# OUTPUT.net
KiCad netlist of a schematic drawn in Altium Designer
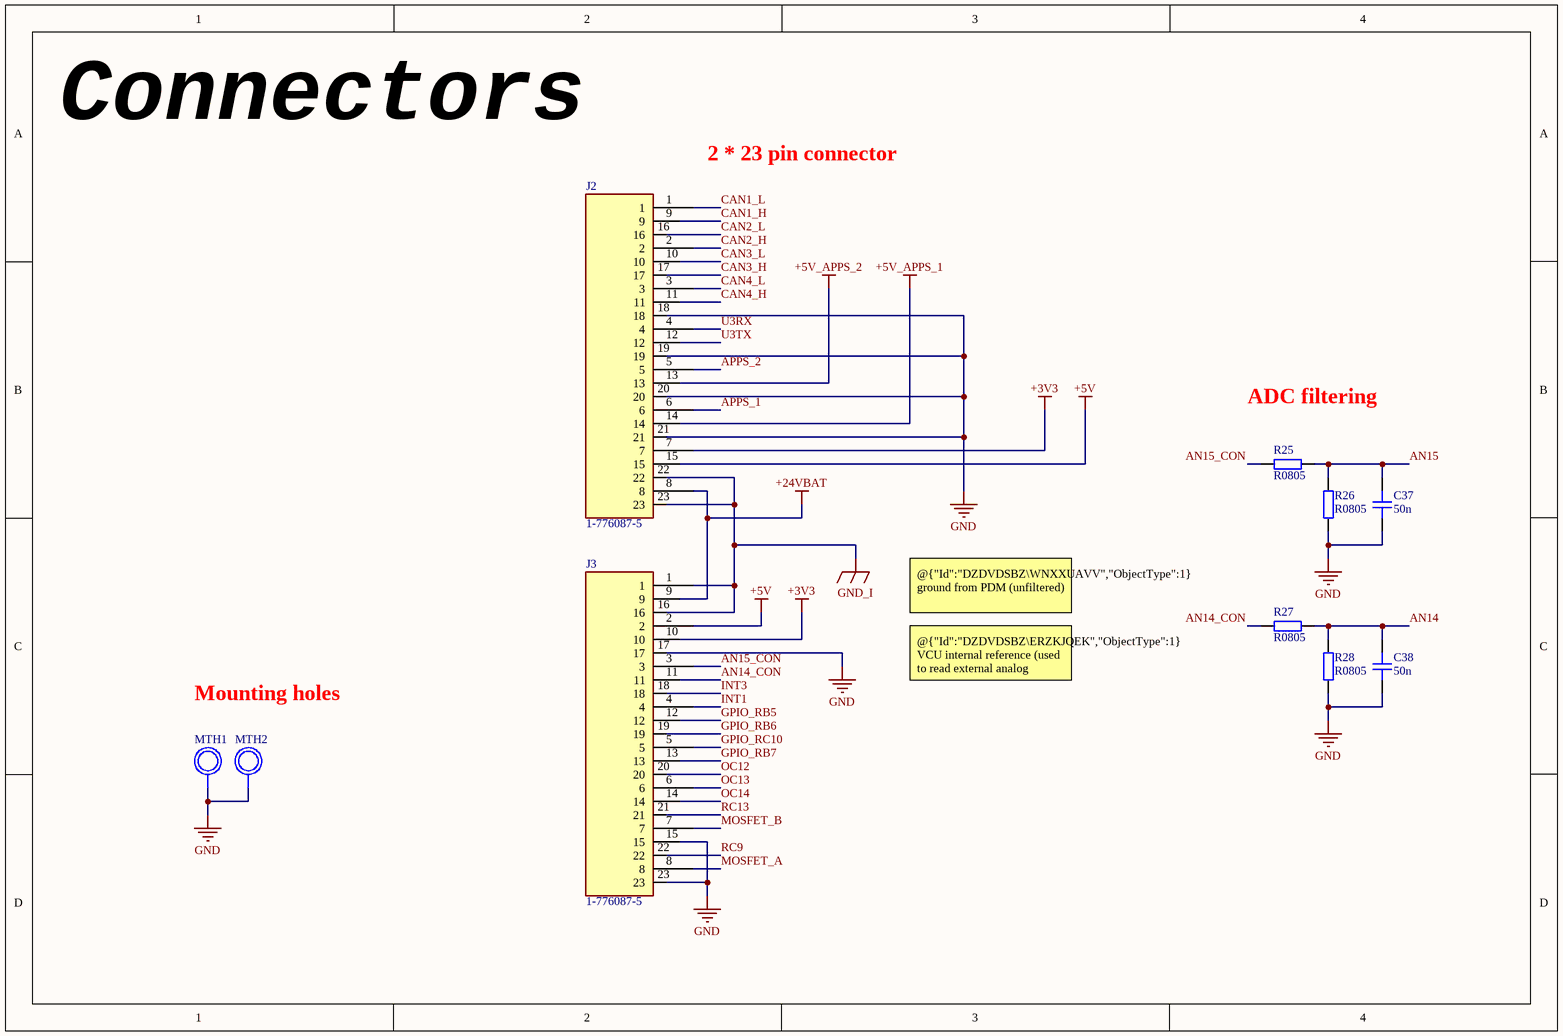
[diagram p0: OUTPUT.SchDoc]

(export (version "E")
  (design (tool "Eeschema 10.0.6"))
  (components
    (comp (ref "C37")
      (value "50n")
      (footprint "CAP_0805")
      (description "Capacitor SMD 0805 10V")
      (libsource (lib "Schematic-Lib-PhilsLab") (part "CAP_0805_10V"))
    )
    (comp (ref "C38")
      (value "50n")
      (footprint "CAP_0805")
      (description "Capacitor SMD 0805 10V")
      (libsource (lib "Schematic-Lib-PhilsLab") (part "CAP_0805_10V"))
    )
    (comp (ref "J2")
      (value "1-776087-5")
      (footprint "1-776087-5")
      (description "CONN HDR 23POS R/A W/GASKET AU")
      (libsource (lib "Pedro_Integrated_Library") (part "1-776087-5"))
    )
    (comp (ref "J3")
      (value "1-776087-5")
      (footprint "1-776087-5")
      (description "CONN HDR 23POS R/A W/GASKET AU")
      (libsource (lib "Pedro_Integrated_Library") (part "1-776087-5"))
    )
    (comp (ref "MTH1")
      (value "Mounting_Hole_3.5mm")
      (footprint "Mounting_Hole_3.5mm")
      (libsource (lib "Pedro_Integrated_Library") (part "Mounting_Hole_3.5mm"))
    )
    (comp (ref "MTH2")
      (value "Mounting_Hole_3.5mm")
      (footprint "Mounting_Hole_3.5mm")
      (libsource (lib "Pedro_Integrated_Library") (part "Mounting_Hole_3.5mm"))
    )
    (comp (ref "R25")
      (value "R0805")
      (footprint "RES_0805")
      (description "Resistor SMD 0805")
      (libsource (lib "Schematic-Lib-PhilsLab") (part "RES_0805"))
    )
    (comp (ref "R26")
      (value "R0805")
      (footprint "RES_0805")
      (description "Resistor SMD 0805")
      (libsource (lib "Schematic-Lib-PhilsLab") (part "RES_0805"))
    )
    (comp (ref "R27")
      (value "R0805")
      (footprint "RES_0805")
      (description "Resistor SMD 0805")
      (libsource (lib "Schematic-Lib-PhilsLab") (part "RES_0805"))
    )
    (comp (ref "R28")
      (value "R0805")
      (footprint "RES_0805")
      (description "Resistor SMD 0805")
      (libsource (lib "Schematic-Lib-PhilsLab") (part "RES_0805"))
    )
  )
  (nets
    (net (code "1") (name "+3V3") (class "Default")
      (node (ref "J2") (pin "7") (pinfunction "7_7") (pintype "passive"))
      (node (ref "J3") (pin "10") (pinfunction "10_10") (pintype "passive"))
    )
    (net (code "2") (name "+5V") (class "Default")
      (node (ref "J2") (pin "15") (pinfunction "15_15") (pintype "passive"))
      (node (ref "J3") (pin "2") (pinfunction "2_2") (pintype "passive"))
    )
    (net (code "3") (name "+5V_APPS_1") (class "Default")
      (node (ref "J2") (pin "14") (pinfunction "14_14") (pintype "passive"))
    )
    (net (code "4") (name "+5V_APPS_2") (class "Default")
      (node (ref "J2") (pin "13") (pinfunction "13_13") (pintype "passive"))
    )
    (net (code "5") (name "+24VBAT") (class "Default")
      (node (ref "J2") (pin "8") (pinfunction "8_8") (pintype "passive"))
      (node (ref "J3") (pin "9") (pinfunction "9_9") (pintype "passive"))
    )
    (net (code "6") (name "/AN14") (class "Default")
      (node (ref "C38") (pin "1") (pinfunction "1_1") (pintype "passive"))
      (node (ref "R27") (pin "1") (pinfunction "1_1") (pintype "passive"))
      (node (ref "R28") (pin "1") (pinfunction "1_1") (pintype "passive"))
    )
    (net (code "7") (name "/AN14_CON") (class "Default")
      (node (ref "J3") (pin "11") (pinfunction "11_11") (pintype "passive"))
      (node (ref "R27") (pin "2") (pinfunction "2_2") (pintype "passive"))
    )
    (net (code "8") (name "/AN15") (class "Default")
      (node (ref "C37") (pin "1") (pinfunction "1_1") (pintype "passive"))
      (node (ref "R25") (pin "1") (pinfunction "1_1") (pintype "passive"))
      (node (ref "R26") (pin "1") (pinfunction "1_1") (pintype "passive"))
    )
    (net (code "9") (name "/AN15_CON") (class "Default")
      (node (ref "J3") (pin "3") (pinfunction "3_3") (pintype "passive"))
      (node (ref "R25") (pin "2") (pinfunction "2_2") (pintype "passive"))
    )
    (net (code "10") (name "/APPS_1") (class "Default")
      (node (ref "J2") (pin "6") (pinfunction "6_6") (pintype "passive"))
    )
    (net (code "11") (name "/APPS_2") (class "Default")
      (node (ref "J2") (pin "5") (pinfunction "5_5") (pintype "passive"))
    )
    (net (code "12") (name "/CAN1_H") (class "Default")
      (node (ref "J2") (pin "9") (pinfunction "9_9") (pintype "passive"))
    )
    (net (code "13") (name "/CAN1_L") (class "Default")
      (node (ref "J2") (pin "1") (pinfunction "1_1") (pintype "passive"))
    )
    (net (code "14") (name "/CAN2_H") (class "Default")
      (node (ref "J2") (pin "2") (pinfunction "2_2") (pintype "passive"))
    )
    (net (code "15") (name "/CAN2_L") (class "Default")
      (node (ref "J2") (pin "16") (pinfunction "16_16") (pintype "passive"))
    )
    (net (code "16") (name "/CAN3_H") (class "Default")
      (node (ref "J2") (pin "17") (pinfunction "17_17") (pintype "passive"))
    )
    (net (code "17") (name "/CAN3_L") (class "Default")
      (node (ref "J2") (pin "10") (pinfunction "10_10") (pintype "passive"))
    )
    (net (code "18") (name "/CAN4_H") (class "Default")
      (node (ref "J2") (pin "11") (pinfunction "11_11") (pintype "passive"))
    )
    (net (code "19") (name "/CAN4_L") (class "Default")
      (node (ref "J2") (pin "3") (pinfunction "3_3") (pintype "passive"))
    )
    (net (code "20") (name "/GPIO_RB5") (class "Default")
      (node (ref "J3") (pin "12") (pinfunction "12_12") (pintype "passive"))
    )
    (net (code "21") (name "/GPIO_RB6") (class "Default")
      (node (ref "J3") (pin "19") (pinfunction "19_19") (pintype "passive"))
    )
    (net (code "22") (name "/GPIO_RB7") (class "Default")
      (node (ref "J3") (pin "13") (pinfunction "13_13") (pintype "passive"))
    )
    (net (code "23") (name "/GPIO_RC10") (class "Default")
      (node (ref "J3") (pin "5") (pinfunction "5_5") (pintype "passive"))
    )
    (net (code "24") (name "/INT1") (class "Default")
      (node (ref "J3") (pin "4") (pinfunction "4_4") (pintype "passive"))
    )
    (net (code "25") (name "/INT3") (class "Default")
      (node (ref "J3") (pin "18") (pinfunction "18_18") (pintype "passive"))
    )
    (net (code "26") (name "/MOSFET_A") (class "Default")
      (node (ref "J3") (pin "8") (pinfunction "8_8") (pintype "passive"))
    )
    (net (code "27") (name "/MOSFET_B") (class "Default")
      (node (ref "J3") (pin "7") (pinfunction "7_7") (pintype "passive"))
    )
    (net (code "28") (name "/OC12") (class "Default")
      (node (ref "J3") (pin "20") (pinfunction "20_20") (pintype "passive"))
    )
    (net (code "29") (name "/OC13") (class "Default")
      (node (ref "J3") (pin "6") (pinfunction "6_6") (pintype "passive"))
    )
    (net (code "30") (name "/OC14") (class "Default")
      (node (ref "J3") (pin "14") (pinfunction "14_14") (pintype "passive"))
    )
    (net (code "31") (name "/RC9") (class "Default")
      (node (ref "J3") (pin "22") (pinfunction "22_22") (pintype "passive"))
    )
    (net (code "32") (name "/RC13") (class "Default")
      (node (ref "J3") (pin "21") (pinfunction "21_21") (pintype "passive"))
    )
    (net (code "33") (name "/U3RX") (class "Default")
      (node (ref "J2") (pin "4") (pinfunction "4_4") (pintype "passive"))
    )
    (net (code "34") (name "/U3TX") (class "Default")
      (node (ref "J2") (pin "12") (pinfunction "12_12") (pintype "passive"))
    )
    (net (code "35") (name "GND") (class "Default")
      (node (ref "C37") (pin "2") (pinfunction "2_2") (pintype "passive"))
      (node (ref "C38") (pin "2") (pinfunction "2_2") (pintype "passive"))
      (node (ref "J2") (pin "18") (pinfunction "18_18") (pintype "passive"))
      (node (ref "J2") (pin "19") (pinfunction "19_19") (pintype "passive"))
      (node (ref "J2") (pin "20") (pinfunction "20_20") (pintype "passive"))
      (node (ref "J2") (pin "21") (pinfunction "21_21") (pintype "passive"))
      (node (ref "J3") (pin "15") (pinfunction "15_15") (pintype "passive"))
      (node (ref "J3") (pin "17") (pinfunction "17_17") (pintype "passive"))
      (node (ref "J3") (pin "23") (pinfunction "23_23") (pintype "passive"))
      (node (ref "MTH1") (pin "1") (pinfunction "1_1") (pintype "passive"))
      (node (ref "MTH2") (pin "1") (pinfunction "1_1") (pintype "passive"))
      (node (ref "R26") (pin "2") (pinfunction "2_2") (pintype "passive"))
      (node (ref "R28") (pin "2") (pinfunction "2_2") (pintype "passive"))
    )
    (net (code "36") (name "GND_I") (class "Default")
      (node (ref "J2") (pin "22") (pinfunction "22_22") (pintype "passive"))
      (node (ref "J2") (pin "23") (pinfunction "23_23") (pintype "passive"))
      (node (ref "J3") (pin "1") (pinfunction "1_1") (pintype "passive"))
      (node (ref "J3") (pin "16") (pinfunction "16_16") (pintype "passive"))
    )
  )
)
